# untitled.net
KiCad netlist of a schematic drawn in EAGLE
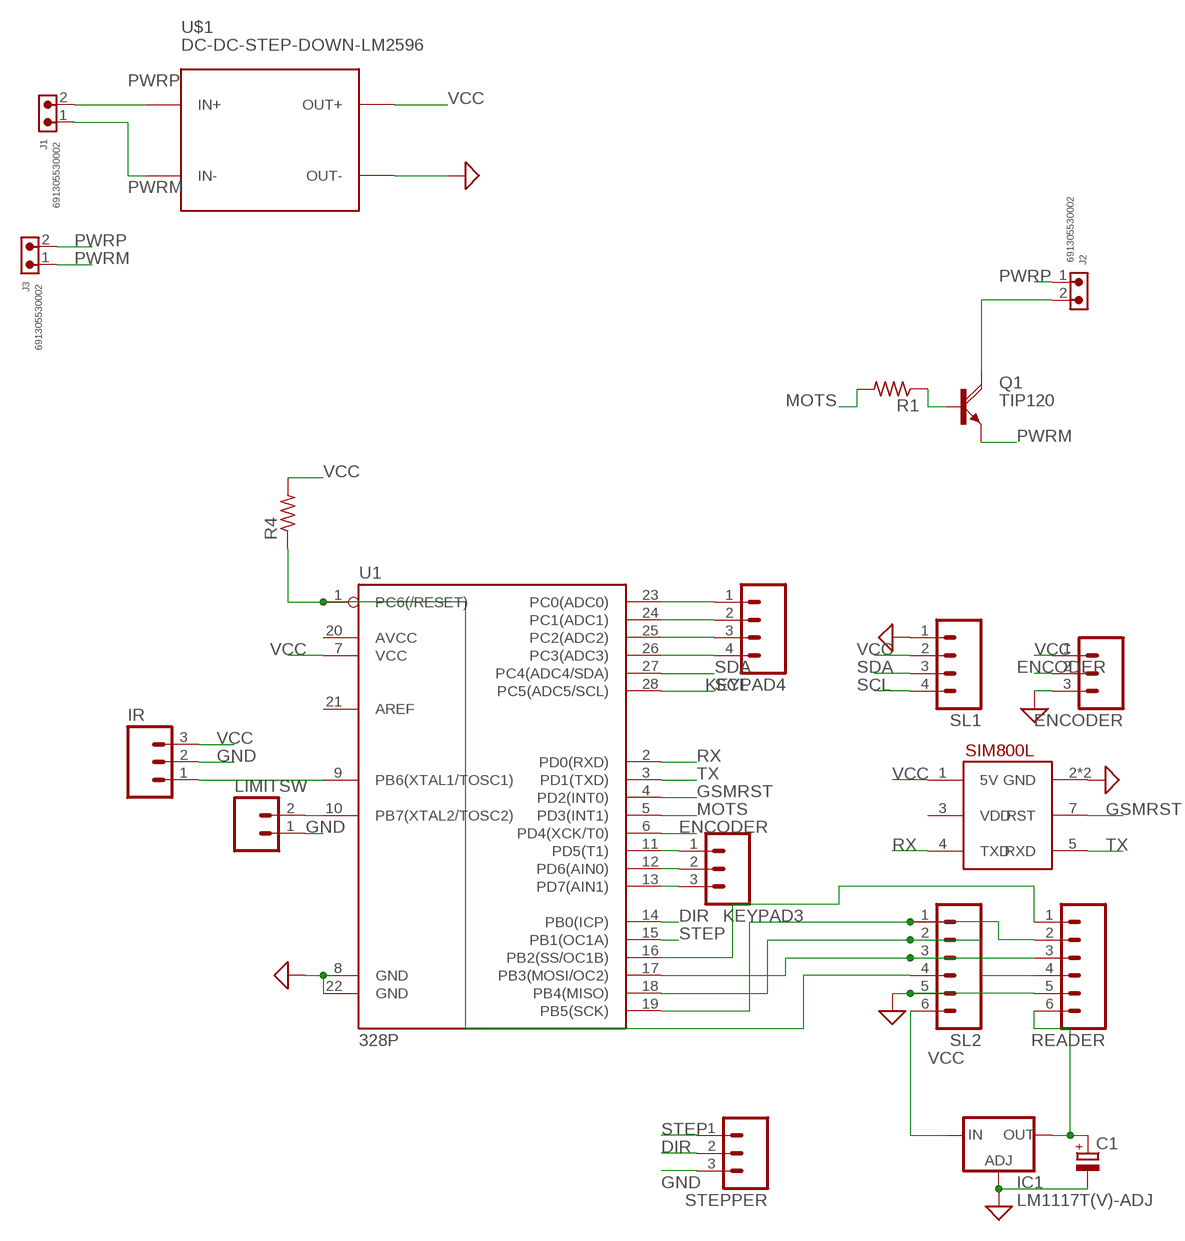
[diagram p0: schematic, sheet 1]

(export (version "E")
  (design (tool "Eeschema 10.0.6"))
  (components
    (comp (ref "C1")
      (value "CPOL-EUE5-10.5")
      (footprint "eagle-import:E5-10,5")
      (libsource (lib "eagle-import") (part "CPOL-EUE5-10.5"))
    )
    (comp (ref "ENCODER")
      (value "M03")
      (footprint "eagle-import:03P")
      (libsource (lib "eagle-import") (part "M03"))
    )
    (comp (ref "IC1")
      (value "LM1117T(V)-ADJ")
      (footprint "eagle-import:TO220V")
      (fields (field (name "MF") "Texas Instruments") (field (name "MPN") "LM1777T-ADJ"))
      (libsource (lib "eagle-import") (part "LM1117?-ADJT(V)"))
    )
    (comp (ref "IR")
      (value "M03")
      (footprint "eagle-import:03P")
      (libsource (lib "eagle-import") (part "M03"))
    )
    (comp (ref "J1")
      (value "691305530002")
      (footprint "eagle-import:691305530002")
      (libsource (lib "eagle-import") (part "691305530002"))
    )
    (comp (ref "J2")
      (value "691305530002")
      (footprint "eagle-import:691305530002")
      (libsource (lib "eagle-import") (part "691305530002"))
    )
    (comp (ref "J3")
      (value "691305530002")
      (footprint "eagle-import:691305530002")
      (libsource (lib "eagle-import") (part "691305530002"))
    )
    (comp (ref "KEYPAD3")
      (value "M03")
      (footprint "eagle-import:03P")
      (libsource (lib "eagle-import") (part "M03"))
    )
    (comp (ref "KEYPAD4")
      (value "M04")
      (footprint "eagle-import:04P")
      (libsource (lib "eagle-import") (part "M04"))
    )
    (comp (ref "LIMITSW")
      (value "M02")
      (footprint "eagle-import:02P")
      (libsource (lib "eagle-import") (part "M02"))
    )
    (comp (ref "Q1")
      (value "TIP120")
      (footprint "eagle-import:TO220AH")
      (libsource (lib "eagle-import") (part "TIP120"))
    )
    (comp (ref "R1")
      (value "R-US_0207/15")
      (footprint "eagle-import:0207_15")
      (libsource (lib "eagle-import") (part "adafruit_R-US_0207/15"))
    )
    (comp (ref "R4")
      (value "R-US_0207/10")
      (footprint "eagle-import:0207_10")
      (libsource (lib "eagle-import") (part "R-US_0207/10"))
    )
    (comp (ref "READER")
      (value "M06")
      (footprint "eagle-import:06P")
      (libsource (lib "eagle-import") (part "M06"))
    )
    (comp (ref "SL1")
      (value "M04")
      (footprint "eagle-import:04P")
      (libsource (lib "eagle-import") (part "M04"))
    )
    (comp (ref "SL2")
      (value "M06")
      (footprint "eagle-import:06P")
      (libsource (lib "eagle-import") (part "M06"))
    )
    (comp (ref "STEPPER")
      (value "M03")
      (footprint "eagle-import:03P")
      (libsource (lib "eagle-import") (part "M03"))
    )
    (comp (ref "U$1")
      (value "DC-DC-STEP-DOWN-LM2596")
      (footprint "eagle-import:DC-DC-STEP-DOWN-LM2596")
      (libsource (lib "eagle-import") (part "DC-DC-STEP-DOWN-LM2596"))
    )
    (comp (ref "U$2")
      (value "SIM800L")
      (footprint "eagle-import:SIP")
      (libsource (lib "eagle-import") (part "SIM800L"))
    )
    (comp (ref "U1")
      (value "328P")
      (footprint "eagle-import:DIP28")
      (libsource (lib "eagle-import") (part "ATMEGA328P_PDIP"))
    )
  )
  (nets
    (net (code "1") (name "/DIR") (class "Default")
      (node (ref "STEPPER") (pin "2") (pinfunction "2_2") (pintype "passive"))
      (node (ref "U1") (pin "14") (pinfunction "PB0(ICP)_14") (pintype "bidirectional"))
    )
    (net (code "2") (name "/ENCODER") (class "Default")
      (node (ref "ENCODER") (pin "2") (pinfunction "2_2") (pintype "passive"))
      (node (ref "U1") (pin "6") (pinfunction "PD4(XCK/T0)_6") (pintype "bidirectional"))
    )
    (net (code "3") (name "/GSMRST") (class "Default")
      (node (ref "U$2") (pin "7") (pinfunction "RST_7") (pintype "bidirectional"))
      (node (ref "U1") (pin "4") (pinfunction "PD2(INT0)_4") (pintype "bidirectional"))
    )
    (net (code "4") (name "/MOTS") (class "Default")
      (node (ref "R1") (pin "2") (pinfunction "2_2") (pintype "passive"))
      (node (ref "U1") (pin "5") (pinfunction "PD3(INT1)_5") (pintype "bidirectional"))
    )
    (net (code "5") (name "/PWRM") (class "Default")
      (node (ref "J1") (pin "1") (pinfunction "1_1") (pintype "passive"))
      (node (ref "J3") (pin "1") (pinfunction "1_1") (pintype "passive"))
      (node (ref "Q1") (pin "E") (pinfunction "E_E") (pintype "passive"))
      (node (ref "U$1") (pin "IN-") (pinfunction "IN-_IN-") (pintype "bidirectional"))
    )
    (net (code "6") (name "/PWRP") (class "Default")
      (node (ref "J1") (pin "2") (pinfunction "2_2") (pintype "passive"))
      (node (ref "J2") (pin "1") (pinfunction "1_1") (pintype "passive"))
      (node (ref "J3") (pin "2") (pinfunction "2_2") (pintype "passive"))
      (node (ref "U$1") (pin "IN+") (pinfunction "IN+_IN+") (pintype "bidirectional"))
    )
    (net (code "7") (name "/RX") (class "Default")
      (node (ref "U$2") (pin "4") (pinfunction "TXD_4") (pintype "bidirectional"))
      (node (ref "U1") (pin "2") (pinfunction "PD0(RXD)_2") (pintype "bidirectional"))
    )
    (net (code "8") (name "/SCL") (class "Default")
      (node (ref "SL1") (pin "4") (pinfunction "4_4") (pintype "passive"))
      (node (ref "U1") (pin "28") (pinfunction "PC5(ADC5/SCL)_28") (pintype "bidirectional"))
    )
    (net (code "9") (name "/SDA") (class "Default")
      (node (ref "SL1") (pin "3") (pinfunction "3_3") (pintype "passive"))
      (node (ref "U1") (pin "27") (pinfunction "PC4(ADC4/SDA)_27") (pintype "bidirectional"))
    )
    (net (code "10") (name "/STEP") (class "Default")
      (node (ref "STEPPER") (pin "1") (pinfunction "1_1") (pintype "passive"))
      (node (ref "U1") (pin "15") (pinfunction "PB1(OC1A)_15") (pintype "bidirectional"))
    )
    (net (code "11") (name "/TX") (class "Default")
      (node (ref "U$2") (pin "5") (pinfunction "RXD_5") (pintype "bidirectional"))
      (node (ref "U1") (pin "3") (pinfunction "PD1(TXD)_3") (pintype "bidirectional"))
    )
    (net (code "12") (name "/VCC") (class "Default")
      (node (ref "ENCODER") (pin "1") (pinfunction "1_1") (pintype "passive"))
      (node (ref "IC1") (pin "3") (pinfunction "IN_3") (pintype "input"))
      (node (ref "IR") (pin "3") (pinfunction "3_3") (pintype "passive"))
      (node (ref "R4") (pin "2") (pinfunction "2_2") (pintype "passive"))
      (node (ref "SL1") (pin "2") (pinfunction "2_2") (pintype "passive"))
      (node (ref "SL2") (pin "6") (pinfunction "6_6") (pintype "passive"))
      (node (ref "U$1") (pin "OUT+") (pinfunction "OUT+_OUT+") (pintype "bidirectional"))
      (node (ref "U$2") (pin "1") (pinfunction "5V_1") (pintype "bidirectional"))
      (node (ref "U1") (pin "7") (pinfunction "VCC_7") (pintype "bidirectional"))
    )
    (net (code "13") (name "Net-(IC1-OUT)") (class "Default")
      (node (ref "C1") (pin "+") (pinfunction "+_+") (pintype "passive"))
      (node (ref "IC1") (pin "2") (pinfunction "OUT_2") (pintype "passive"))
      (node (ref "READER") (pin "6") (pinfunction "6_6") (pintype "passive"))
    )
    (net (code "14") (name "Net-(J2-Pad2)") (class "Default")
      (node (ref "J2") (pin "2") (pinfunction "2_2") (pintype "passive"))
      (node (ref "Q1") (pin "C") (pinfunction "C_C") (pintype "passive"))
    )
    (net (code "15") (name "Net-(Q1-PadB)") (class "Default")
      (node (ref "Q1") (pin "B") (pinfunction "B_B") (pintype "passive"))
      (node (ref "R1") (pin "1") (pinfunction "1_1") (pintype "passive"))
    )
    (net (code "16") (name "Net-(U1-PB2(SS{slash}OC1B))") (class "Default")
      (node (ref "READER") (pin "1") (pinfunction "1_1") (pintype "passive"))
      (node (ref "U1") (pin "16") (pinfunction "PB2(SS/OC1B)_16") (pintype "bidirectional"))
    )
    (net (code "17") (name "Net-(U1-PB3(MOSI{slash}OC2))") (class "Default")
      (node (ref "READER") (pin "3") (pinfunction "3_3") (pintype "passive"))
      (node (ref "SL2") (pin "3") (pinfunction "3_3") (pintype "passive"))
      (node (ref "U1") (pin "17") (pinfunction "PB3(MOSI/OC2)_17") (pintype "bidirectional"))
    )
    (net (code "18") (name "Net-(U1-PB4(MISO))") (class "Default")
      (node (ref "READER") (pin "4") (pinfunction "4_4") (pintype "passive"))
      (node (ref "SL2") (pin "2") (pinfunction "2_2") (pintype "passive"))
      (node (ref "U1") (pin "18") (pinfunction "PB4(MISO)_18") (pintype "bidirectional"))
    )
    (net (code "19") (name "Net-(U1-PB5(SCK))") (class "Default")
      (node (ref "READER") (pin "2") (pinfunction "2_2") (pintype "passive"))
      (node (ref "SL2") (pin "1") (pinfunction "1_1") (pintype "passive"))
      (node (ref "U1") (pin "19") (pinfunction "PB5(SCK)_19") (pintype "bidirectional"))
    )
    (net (code "20") (name "Net-(U1-PB6(XTAL1{slash}TOSC1))") (class "Default")
      (node (ref "IR") (pin "1") (pinfunction "1_1") (pintype "passive"))
      (node (ref "U1") (pin "9") (pinfunction "PB6(XTAL1/TOSC1)_9") (pintype "bidirectional"))
    )
    (net (code "21") (name "Net-(U1-PB7(XTAL2{slash}TOSC2))") (class "Default")
      (node (ref "LIMITSW") (pin "2") (pinfunction "2_2") (pintype "passive"))
      (node (ref "U1") (pin "10") (pinfunction "PB7(XTAL2/TOSC2)_10") (pintype "bidirectional"))
    )
    (net (code "22") (name "Net-(U1-PC0(ADC0))") (class "Default")
      (node (ref "KEYPAD4") (pin "1") (pinfunction "1_1") (pintype "passive"))
      (node (ref "U1") (pin "23") (pinfunction "PC0(ADC0)_23") (pintype "bidirectional"))
    )
    (net (code "23") (name "Net-(U1-PC1(ADC1))") (class "Default")
      (node (ref "KEYPAD4") (pin "2") (pinfunction "2_2") (pintype "passive"))
      (node (ref "U1") (pin "24") (pinfunction "PC1(ADC1)_24") (pintype "bidirectional"))
    )
    (net (code "24") (name "Net-(U1-PC2(ADC2))") (class "Default")
      (node (ref "KEYPAD4") (pin "3") (pinfunction "3_3") (pintype "passive"))
      (node (ref "U1") (pin "25") (pinfunction "PC2(ADC2)_25") (pintype "bidirectional"))
    )
    (net (code "25") (name "Net-(U1-PC3(ADC3))") (class "Default")
      (node (ref "KEYPAD4") (pin "4") (pinfunction "4_4") (pintype "passive"))
      (node (ref "U1") (pin "26") (pinfunction "PC3(ADC3)_26") (pintype "bidirectional"))
    )
    (net (code "26") (name "Net-(U1-PC6({slash}RESET))") (class "Default")
      (node (ref "R4") (pin "1") (pinfunction "1_1") (pintype "passive"))
      (node (ref "SL2") (pin "4") (pinfunction "4_4") (pintype "passive"))
      (node (ref "U1") (pin "1") (pinfunction "PC6(/RESET)_1") (pintype "bidirectional"))
    )
    (net (code "27") (name "Net-(U1-PD5(T1))") (class "Default")
      (node (ref "KEYPAD3") (pin "1") (pinfunction "1_1") (pintype "passive"))
      (node (ref "U1") (pin "11") (pinfunction "PD5(T1)_11") (pintype "bidirectional"))
    )
    (net (code "28") (name "Net-(U1-PD6(AIN0))") (class "Default")
      (node (ref "KEYPAD3") (pin "2") (pinfunction "2_2") (pintype "passive"))
      (node (ref "U1") (pin "12") (pinfunction "PD6(AIN0)_12") (pintype "bidirectional"))
    )
    (net (code "29") (name "Net-(U1-PD7(AIN1))") (class "Default")
      (node (ref "KEYPAD3") (pin "3") (pinfunction "3_3") (pintype "passive"))
      (node (ref "U1") (pin "13") (pinfunction "PD7(AIN1)_13") (pintype "bidirectional"))
    )
    (net (code "30") (name "SUP") (class "Default")
      (node (ref "C1") (pin "-") (pinfunction "-_-") (pintype "passive"))
      (node (ref "ENCODER") (pin "3") (pinfunction "3_3") (pintype "passive"))
      (node (ref "IC1") (pin "1") (pinfunction "ADJ_1") (pintype "input"))
      (node (ref "IR") (pin "2") (pinfunction "2_2") (pintype "passive"))
      (node (ref "LIMITSW") (pin "1") (pinfunction "1_1") (pintype "passive"))
      (node (ref "READER") (pin "5") (pinfunction "5_5") (pintype "passive"))
      (node (ref "SL1") (pin "1") (pinfunction "1_1") (pintype "passive"))
      (node (ref "SL2") (pin "5") (pinfunction "5_5") (pintype "passive"))
      (node (ref "STEPPER") (pin "3") (pinfunction "3_3") (pintype "passive"))
      (node (ref "U$1") (pin "OUT-") (pinfunction "OUT-_OUT-") (pintype "bidirectional"))
      (node (ref "U$2") (pin "2") (pinfunction "GND_2") (pintype "bidirectional"))
      (node (ref "U$2") (pin "6") (pinfunction "GND_6") (pintype "bidirectional"))
      (node (ref "U1") (pin "22") (pinfunction "GND_22") (pintype "bidirectional"))
      (node (ref "U1") (pin "8") (pinfunction "GND_8") (pintype "bidirectional"))
    )
    (net (code "31") (name "unconnected-(U$2-VDD-Pad3)") (class "Default")
      (node (ref "U$2") (pin "3") (pinfunction "VDD_3") (pintype "bidirectional"))
    )
    (net (code "32") (name "unconnected-(U1-AREF-Pad21)") (class "Default")
      (node (ref "U1") (pin "21") (pinfunction "AREF_21") (pintype "bidirectional"))
    )
    (net (code "33") (name "unconnected-(U1-AVCC-Pad20)") (class "Default")
      (node (ref "U1") (pin "20") (pinfunction "AVCC_20") (pintype "bidirectional"))
    )
  )
)
